# ttgo-diy.net
KiCad netlist of a schematic drawn in EAGLE
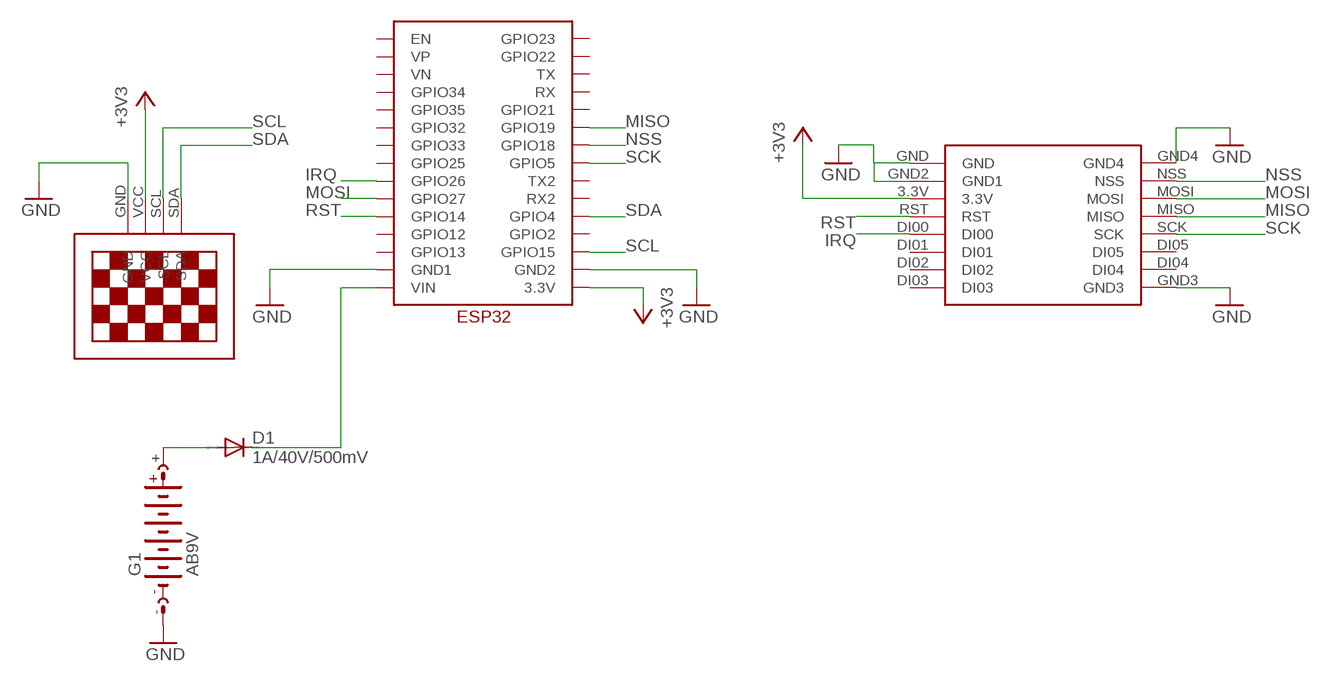
[diagram p0: schematic, sheet 1]

(export (version "E")
  (design (tool "Eeschema 10.0.6"))
  (components
    (comp (ref "D1")
      (value "1A/40V/500mV")
      (footprint "eagle-import:DO35-10")
      (libsource (lib "eagle-import") (part "1N4148DO35-10"))
    )
    (comp (ref "G1")
      (value "AB9V")
      (footprint "eagle-import:AB9V")
      (libsource (lib "eagle-import") (part "AB9V"))
    )
    (comp (ref "U$1")
      (value "LORA-02DIL")
      (footprint "eagle-import:DIL8X11")
      (libsource (lib "eagle-import") (part "LORA-02DIL"))
    )
    (comp (ref "U$2")
      (value "ESP32")
      (footprint "eagle-import:ESP32")
      (libsource (lib "eagle-import") (part "ESP32"))
    )
    (comp (ref "U$3")
      (value "13\"OLED13\"OLED")
      (footprint "eagle-import:1.3_OLED")
      (libsource (lib "eagle-import") (part "13{dblquote}OLED13{dblquote}OLED"))
    )
  )
  (nets
    (net (code "1") (name "+3V3") (class "Default")
      (node (ref "U$1") (pin "3.3V") (pinfunction "3.3V_3.3V") (pintype "power_in"))
      (node (ref "U$2") (pin "3.3V") (pinfunction "3.3V_3.3V") (pintype "bidirectional"))
      (node (ref "U$3") (pin "VCC") (pinfunction "VCC_VCC") (pintype "bidirectional"))
    )
    (net (code "2") (name "/IRQ") (class "Default")
      (node (ref "U$1") (pin "DI00") (pinfunction "DI00_DI00") (pintype "bidirectional"))
      (node (ref "U$2") (pin "GPIO26") (pinfunction "GPIO26_GPIO26") (pintype "bidirectional"))
    )
    (net (code "3") (name "/MISO") (class "Default")
      (node (ref "U$1") (pin "MISO") (pinfunction "MISO_MISO") (pintype "input"))
      (node (ref "U$2") (pin "GPIO19") (pinfunction "GPIO19_GPIO19") (pintype "bidirectional"))
    )
    (net (code "4") (name "/MOSI") (class "Default")
      (node (ref "U$1") (pin "MOSI") (pinfunction "MOSI_MOSI") (pintype "output"))
      (node (ref "U$2") (pin "GPIO27") (pinfunction "GPIO27_GPIO27") (pintype "bidirectional"))
    )
    (net (code "5") (name "/NSS") (class "Default")
      (node (ref "U$1") (pin "NSS") (pinfunction "NSS_NSS") (pintype "input"))
      (node (ref "U$2") (pin "GPIO18") (pinfunction "GPIO18_GPIO18") (pintype "bidirectional"))
    )
    (net (code "6") (name "/RST") (class "Default")
      (node (ref "U$1") (pin "RST") (pinfunction "RST_RST") (pintype "input"))
      (node (ref "U$2") (pin "GPIO14") (pinfunction "GPIO14_GPIO14") (pintype "bidirectional"))
    )
    (net (code "7") (name "/SCK") (class "Default")
      (node (ref "U$1") (pin "SCK") (pinfunction "SCK_SCK") (pintype "open_collector"))
      (node (ref "U$2") (pin "GPIO5") (pinfunction "GPIO5_GPIO5") (pintype "bidirectional"))
    )
    (net (code "8") (name "/SCL") (class "Default")
      (node (ref "U$2") (pin "GPIO15") (pinfunction "GPIO15_GPIO15") (pintype "bidirectional"))
      (node (ref "U$3") (pin "SCL") (pinfunction "SCL_SCL") (pintype "bidirectional"))
    )
    (net (code "9") (name "/SDA") (class "Default")
      (node (ref "U$2") (pin "GPIO4") (pinfunction "GPIO4_GPIO4") (pintype "bidirectional"))
      (node (ref "U$3") (pin "SDA") (pinfunction "SDA_SDA") (pintype "bidirectional"))
    )
    (net (code "10") (name "GND") (class "Default")
      (node (ref "G1") (pin "-") (pinfunction "-_-") (pintype "passive"))
      (node (ref "U$1") (pin "GND") (pinfunction "GND_GND") (pintype "power_in"))
      (node (ref "U$1") (pin "GND2") (pinfunction "GND1_GND2") (pintype "power_in"))
      (node (ref "U$1") (pin "GND3") (pinfunction "GND3_GND3") (pintype "power_in"))
      (node (ref "U$1") (pin "GND4") (pinfunction "GND4_GND4") (pintype "power_in"))
      (node (ref "U$2") (pin "GND1") (pinfunction "GND1_GND1") (pintype "bidirectional"))
      (node (ref "U$2") (pin "GND2") (pinfunction "GND2_GND2") (pintype "bidirectional"))
      (node (ref "U$3") (pin "GND") (pinfunction "GND_GND") (pintype "bidirectional"))
    )
    (net (code "11") (name "Net-(D1-PadA)") (class "Default")
      (node (ref "D1") (pin "A") (pinfunction "A_A") (pintype "passive"))
      (node (ref "G1") (pin "+") (pinfunction "+_+") (pintype "passive"))
    )
    (net (code "12") (name "Net-(D1-PadC)") (class "Default")
      (node (ref "D1") (pin "C") (pinfunction "C_C") (pintype "passive"))
      (node (ref "U$2") (pin "VIN") (pinfunction "VIN_VIN") (pintype "bidirectional"))
    )
    (net (code "13") (name "unconnected-(U$1-PadDI01)") (class "Default")
      (node (ref "U$1") (pin "DI01") (pinfunction "DI01_DI01") (pintype "bidirectional"))
    )
    (net (code "14") (name "unconnected-(U$1-PadDI02)") (class "Default")
      (node (ref "U$1") (pin "DI02") (pinfunction "DI02_DI02") (pintype "bidirectional"))
    )
    (net (code "15") (name "unconnected-(U$1-PadDI03)") (class "Default")
      (node (ref "U$1") (pin "DI03") (pinfunction "DI03_DI03") (pintype "bidirectional"))
    )
    (net (code "16") (name "unconnected-(U$1-PadDI04)") (class "Default")
      (node (ref "U$1") (pin "DI04") (pinfunction "DI04_DI04") (pintype "bidirectional"))
    )
    (net (code "17") (name "unconnected-(U$1-PadDI05)") (class "Default")
      (node (ref "U$1") (pin "DI05") (pinfunction "DI05_DI05") (pintype "bidirectional"))
    )
    (net (code "18") (name "unconnected-(U$2-PadEN)") (class "Default")
      (node (ref "U$2") (pin "EN") (pinfunction "EN_EN") (pintype "bidirectional"))
    )
    (net (code "19") (name "unconnected-(U$2-PadGPIO2)") (class "Default")
      (node (ref "U$2") (pin "GPIO2") (pinfunction "GPIO2_GPIO2") (pintype "bidirectional"))
    )
    (net (code "20") (name "unconnected-(U$2-PadGPIO12)") (class "Default")
      (node (ref "U$2") (pin "GPIO12") (pinfunction "GPIO12_GPIO12") (pintype "bidirectional"))
    )
    (net (code "21") (name "unconnected-(U$2-PadGPIO13)") (class "Default")
      (node (ref "U$2") (pin "GPIO13") (pinfunction "GPIO13_GPIO13") (pintype "bidirectional"))
    )
    (net (code "22") (name "unconnected-(U$2-PadGPIO21)") (class "Default")
      (node (ref "U$2") (pin "GPIO21") (pinfunction "GPIO21_GPIO21") (pintype "bidirectional"))
    )
    (net (code "23") (name "unconnected-(U$2-PadGPIO22)") (class "Default")
      (node (ref "U$2") (pin "GPIO22") (pinfunction "GPIO22_GPIO22") (pintype "bidirectional"))
    )
    (net (code "24") (name "unconnected-(U$2-PadGPIO23)") (class "Default")
      (node (ref "U$2") (pin "GPIO23") (pinfunction "GPIO23_GPIO23") (pintype "bidirectional"))
    )
    (net (code "25") (name "unconnected-(U$2-PadGPIO25)") (class "Default")
      (node (ref "U$2") (pin "GPIO25") (pinfunction "GPIO25_GPIO25") (pintype "bidirectional"))
    )
    (net (code "26") (name "unconnected-(U$2-PadGPIO32)") (class "Default")
      (node (ref "U$2") (pin "GPIO32") (pinfunction "GPIO32_GPIO32") (pintype "bidirectional"))
    )
    (net (code "27") (name "unconnected-(U$2-PadGPIO33)") (class "Default")
      (node (ref "U$2") (pin "GPIO33") (pinfunction "GPIO33_GPIO33") (pintype "bidirectional"))
    )
    (net (code "28") (name "unconnected-(U$2-PadGPIO34)") (class "Default")
      (node (ref "U$2") (pin "GPIO34") (pinfunction "GPIO34_GPIO34") (pintype "bidirectional"))
    )
    (net (code "29") (name "unconnected-(U$2-PadGPIO35)") (class "Default")
      (node (ref "U$2") (pin "GPIO35") (pinfunction "GPIO35_GPIO35") (pintype "bidirectional"))
    )
    (net (code "30") (name "unconnected-(U$2-PadRX)") (class "Default")
      (node (ref "U$2") (pin "RX") (pinfunction "RX_RX") (pintype "bidirectional"))
    )
    (net (code "31") (name "unconnected-(U$2-PadRX2)") (class "Default")
      (node (ref "U$2") (pin "RX2") (pinfunction "RX2_RX2") (pintype "bidirectional"))
    )
    (net (code "32") (name "unconnected-(U$2-PadTX)") (class "Default")
      (node (ref "U$2") (pin "TX") (pinfunction "TX_TX") (pintype "bidirectional"))
    )
    (net (code "33") (name "unconnected-(U$2-PadTX2)") (class "Default")
      (node (ref "U$2") (pin "TX2") (pinfunction "TX2_TX2") (pintype "bidirectional"))
    )
    (net (code "34") (name "unconnected-(U$2-PadVN)") (class "Default")
      (node (ref "U$2") (pin "VN") (pinfunction "VN_VN") (pintype "bidirectional"))
    )
    (net (code "35") (name "unconnected-(U$2-PadVP)") (class "Default")
      (node (ref "U$2") (pin "VP") (pinfunction "VP_VP") (pintype "bidirectional"))
    )
  )
)
